# MCU.net
KiCad netlist of a schematic drawn in Altium Designer
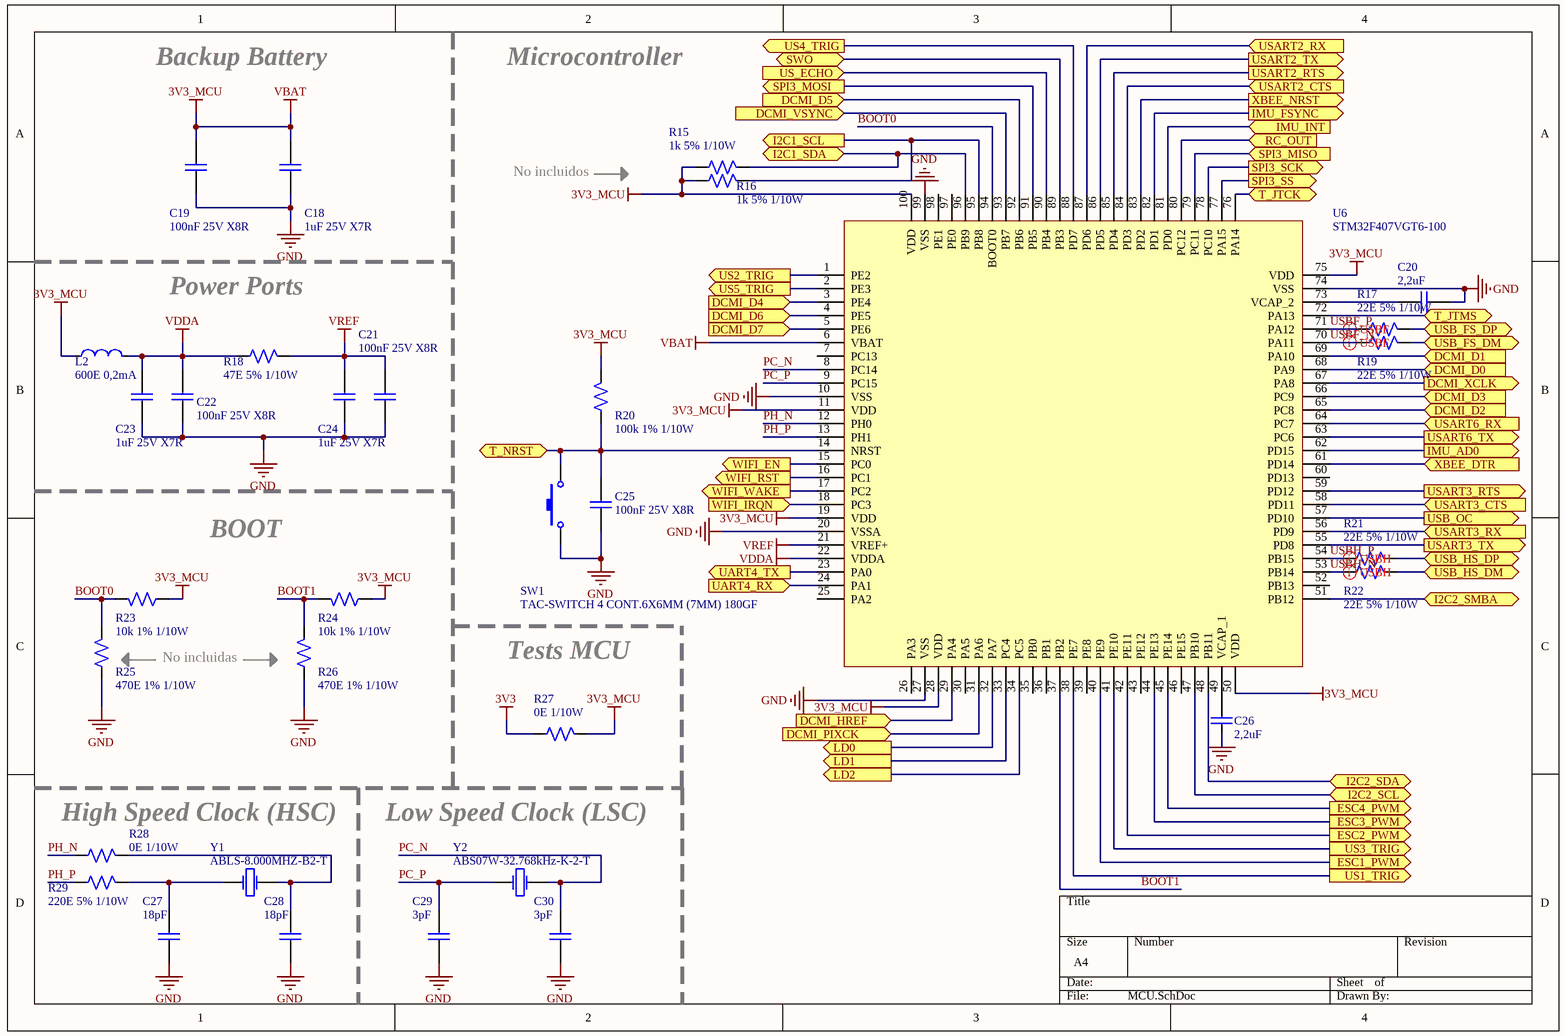
[diagram p0: MCU.SchDoc]

(export (version "E")
  (design (tool "Eeschema 10.0.6"))
  (components
    (comp (ref "C18")
      (value "1uF 25V X7R")
      (footprint "C0603")
      (description "Capacitor de placas paralelas")
      (libsource (lib "HW_Dron_V2") (part "Capacitor"))
    )
    (comp (ref "C19")
      (value "100nF 25V X8R")
      (footprint "C0603")
      (description "Capacitor de placas paralelas")
      (libsource (lib "HW_Dron_V2") (part "Capacitor"))
    )
    (comp (ref "C20")
      (value "2,2uF 16V X7R")
      (footprint "C0603")
      (description "Capacitor de placas paralelas")
      (fields (field (name "VALOR") "2,2uF"))
      (libsource (lib "HW_Dron_V2") (part "Capacitor"))
    )
    (comp (ref "C21")
      (value "100nF 25V X8R")
      (footprint "C0603")
      (description "Capacitor de placas paralelas")
      (libsource (lib "HW_Dron_V2") (part "Capacitor"))
    )
    (comp (ref "C22")
      (value "100nF 25V X8R")
      (footprint "C0603")
      (description "Capacitor de placas paralelas")
      (libsource (lib "HW_Dron_V2") (part "Capacitor"))
    )
    (comp (ref "C23")
      (value "1uF 25V X7R")
      (footprint "C0603")
      (description "Capacitor de placas paralelas")
      (libsource (lib "HW_Dron_V2") (part "Capacitor"))
    )
    (comp (ref "C24")
      (value "1uF 25V X7R")
      (footprint "C0603")
      (description "Capacitor de placas paralelas")
      (libsource (lib "HW_Dron_V2") (part "Capacitor"))
    )
    (comp (ref "C25")
      (value "100nF 25V X8R")
      (footprint "C0603")
      (description "Capacitor de placas paralelas")
      (libsource (lib "HW_Dron_V2") (part "Capacitor"))
    )
    (comp (ref "C26")
      (value "2,2uF 16V X7R")
      (footprint "C0603")
      (description "Capacitor de placas paralelas")
      (fields (field (name "VALOR") "2,2uF"))
      (libsource (lib "HW_Dron_V2") (part "Capacitor"))
    )
    (comp (ref "C27")
      (value "18pF 50V COG 5%")
      (footprint "C0603")
      (description "Capacitor de placas paralelas")
      (fields (field (name "VALOR") "18pF"))
      (libsource (lib "HW_Dron_V2") (part "Capacitor"))
    )
    (comp (ref "C28")
      (value "18pF 50V COG 5%")
      (footprint "C0603")
      (description "Capacitor de placas paralelas")
      (fields (field (name "VALOR") "18pF"))
      (libsource (lib "HW_Dron_V2") (part "Capacitor"))
    )
    (comp (ref "C29")
      (value "3pF 50V COG 5%")
      (footprint "C0603")
      (description "Capacitor de placas paralelas")
      (fields (field (name "VALOR") "3pF"))
      (libsource (lib "HW_Dron_V2") (part "Capacitor"))
    )
    (comp (ref "C30")
      (value "3pF 50V COG 5%")
      (footprint "C0603")
      (description "Capacitor de placas paralelas")
      (fields (field (name "VALOR") "3pF"))
      (libsource (lib "HW_Dron_V2") (part "Capacitor"))
    )
    (comp (ref "L2")
      (value "600E 0,2mA")
      (footprint "L0805")
      (description "Inductor")
      (fields (field (name "VALOR") "600E 0,2mA"))
      (libsource (lib "HW_Dron_V2") (part "Inductor"))
    )
    (comp (ref "R15")
      (value "1k 5% 1/10W")
      (footprint "R0603")
      (description "Resistencia")
      (libsource (lib "HW_Dron_V2") (part "Resistor"))
    )
    (comp (ref "R16")
      (value "1k 5% 1/10W")
      (footprint "R0603")
      (description "Resistencia")
      (libsource (lib "HW_Dron_V2") (part "Resistor"))
    )
    (comp (ref "R17")
      (value "22E 5% 1/10W")
      (footprint "R0603")
      (description "Resistencia")
      (libsource (lib "HW_Dron_V2") (part "Resistor"))
    )
    (comp (ref "R18")
      (value "47E 5% 1/10W")
      (footprint "R0603")
      (description "Resistencia")
      (libsource (lib "HW_Dron_V2") (part "Resistor"))
    )
    (comp (ref "R19")
      (value "22E 5% 1/10W")
      (footprint "R0603")
      (description "Resistencia")
      (libsource (lib "HW_Dron_V2") (part "Resistor"))
    )
    (comp (ref "R20")
      (value "100k 1% 1/10W")
      (footprint "R0603")
      (description "Resistencia")
      (libsource (lib "HW_Dron_V2") (part "Resistor"))
    )
    (comp (ref "R21")
      (value "22E 5% 1/10W")
      (footprint "R0603")
      (description "Resistencia")
      (libsource (lib "HW_Dron_V2") (part "Resistor"))
    )
    (comp (ref "R22")
      (value "22E 5% 1/10W")
      (footprint "R0603")
      (description "Resistencia")
      (libsource (lib "HW_Dron_V2") (part "Resistor"))
    )
    (comp (ref "R23")
      (value "10k 1% 1/10W")
      (footprint "R0603")
      (description "Resistencia")
      (libsource (lib "HW_Dron_V2") (part "Resistor"))
    )
    (comp (ref "R24")
      (value "10k 1% 1/10W")
      (footprint "R0603")
      (description "Resistencia")
      (libsource (lib "HW_Dron_V2") (part "Resistor"))
    )
    (comp (ref "R25")
      (value "470E 1% 1/10W")
      (footprint "R0603")
      (description "Resistencia")
      (libsource (lib "HW_Dron_V2") (part "Resistor"))
    )
    (comp (ref "R26")
      (value "470E 1% 1/10W")
      (footprint "R0603")
      (description "Resistencia")
      (libsource (lib "HW_Dron_V2") (part "Resistor"))
    )
    (comp (ref "R27")
      (value "0E 1/10W")
      (footprint "R0805")
      (description "Resistencia")
      (libsource (lib "HW_Dron_V2") (part "Resistor"))
    )
    (comp (ref "R28")
      (value "0E 1/10W")
      (footprint "R0603")
      (description "Resistencia")
      (libsource (lib "HW_Dron_V2") (part "Resistor"))
    )
    (comp (ref "R29")
      (value "220E 5% 1/10W")
      (footprint "R0603")
      (description "Resistencia")
      (libsource (lib "HW_Dron_V2") (part "Resistor"))
    )
    (comp (ref "SW1")
      (value "TAC-SWITCH 4 CONT.6X6MM (7MM) 180GF")
      (footprint "TAC_SW_4")
      (description "Pulsador de 4 pines")
      (libsource (lib "HW_Dron_V2") (part "TAC_SWITCH_4"))
    )
    (comp (ref "U6")
      (value "STM32F407VGT6-100")
      (footprint "QFP100")
      (description "Microcontrolador STM32F407VGT6 100 pines")
      (libsource (lib "HW_Dron_V2") (part "STM32F407VGT6_100"))
    )
    (comp (ref "Y1")
      (value "ABLS-8.000MHZ-B2-T")
      (footprint "ABLS")
      (description "Resonador cerámico")
      (libsource (lib "HW_Dron_V2") (part "XTAL"))
    )
    (comp (ref "Y2")
      (value "ABS07W-32.768kHz-K-2-T")
      (footprint "ABS07W")
      (description "Resonador cerámico")
      (libsource (lib "HW_Dron_V2") (part "XTAL"))
    )
  )
  (nets
    (net (code "1") (name "/BOOT0") (class "Default")
      (node (ref "R23") (pin "2") (pinfunction "2_2") (pintype "passive"))
      (node (ref "R25") (pin "2") (pinfunction "2_2") (pintype "passive"))
      (node (ref "U6") (pin "94") (pinfunction "BOOT0_94") (pintype "passive"))
    )
    (net (code "2") (name "/BOOT1") (class "Default")
      (node (ref "R24") (pin "2") (pinfunction "2_2") (pintype "passive"))
      (node (ref "R26") (pin "2") (pinfunction "2_2") (pintype "passive"))
      (node (ref "U6") (pin "37") (pinfunction "PB2_37") (pintype "passive"))
    )
    (net (code "3") (name "/DCMI_D0") (class "Default")
      (node (ref "U6") (pin "68") (pinfunction "PA9_68") (pintype "passive"))
    )
    (net (code "4") (name "/DCMI_D1") (class "Default")
      (node (ref "U6") (pin "69") (pinfunction "PA10_69") (pintype "passive"))
    )
    (net (code "5") (name "/DCMI_D2") (class "Default")
      (node (ref "U6") (pin "65") (pinfunction "PC8_65") (pintype "passive"))
    )
    (net (code "6") (name "/DCMI_D3") (class "Default")
      (node (ref "U6") (pin "66") (pinfunction "PC9_66") (pintype "passive"))
    )
    (net (code "7") (name "/DCMI_D4") (class "Default")
      (node (ref "U6") (pin "3") (pinfunction "PE4_3") (pintype "passive"))
    )
    (net (code "8") (name "/DCMI_D5") (class "Default")
      (node (ref "U6") (pin "92") (pinfunction "PB6_92") (pintype "passive"))
    )
    (net (code "9") (name "/DCMI_D6") (class "Default")
      (node (ref "U6") (pin "4") (pinfunction "PE5_4") (pintype "passive"))
    )
    (net (code "10") (name "/DCMI_D7") (class "Default")
      (node (ref "U6") (pin "5") (pinfunction "PE6_5") (pintype "passive"))
    )
    (net (code "11") (name "/DCMI_HREF") (class "Default")
      (node (ref "U6") (pin "29") (pinfunction "PA4_29") (pintype "passive"))
    )
    (net (code "12") (name "/DCMI_PIXCK") (class "Default")
      (node (ref "U6") (pin "31") (pinfunction "PA6_31") (pintype "passive"))
    )
    (net (code "13") (name "/DCMI_VSYNC") (class "Default")
      (node (ref "U6") (pin "93") (pinfunction "PB7_93") (pintype "passive"))
    )
    (net (code "14") (name "/DCMI_XCLK") (class "Default")
      (node (ref "U6") (pin "67") (pinfunction "PA8_67") (pintype "passive"))
    )
    (net (code "15") (name "/ESC1_PWM") (class "Default")
      (node (ref "U6") (pin "40") (pinfunction "PE9_40") (pintype "passive"))
    )
    (net (code "16") (name "/ESC2_PWM") (class "Default")
      (node (ref "U6") (pin "42") (pinfunction "PE11_42") (pintype "passive"))
    )
    (net (code "17") (name "/ESC3_PWM") (class "Default")
      (node (ref "U6") (pin "44") (pinfunction "PE13_44") (pintype "passive"))
    )
    (net (code "18") (name "/ESC4_PWM") (class "Default")
      (node (ref "U6") (pin "45") (pinfunction "PE14_45") (pintype "passive"))
    )
    (net (code "19") (name "/I2C1_SCL") (class "Default")
      (node (ref "R16") (pin "2") (pinfunction "2_2") (pintype "passive"))
      (node (ref "U6") (pin "95") (pinfunction "PB8_95") (pintype "passive"))
    )
    (net (code "20") (name "/I2C1_SDA") (class "Default")
      (node (ref "R15") (pin "2") (pinfunction "2_2") (pintype "passive"))
      (node (ref "U6") (pin "96") (pinfunction "PB9_96") (pintype "passive"))
    )
    (net (code "21") (name "/I2C2_SCL") (class "Default")
      (node (ref "U6") (pin "47") (pinfunction "PB10_47") (pintype "passive"))
    )
    (net (code "22") (name "/I2C2_SDA") (class "Default")
      (node (ref "U6") (pin "48") (pinfunction "PB11_48") (pintype "passive"))
    )
    (net (code "23") (name "/I2C2_SMBA") (class "Default")
      (node (ref "U6") (pin "51") (pinfunction "PB12_51") (pintype "passive"))
    )
    (net (code "24") (name "/IMU_AD0") (class "Default")
      (node (ref "U6") (pin "62") (pinfunction "PD15_62") (pintype "passive"))
    )
    (net (code "25") (name "/IMU_FSYNC") (class "Default")
      (node (ref "U6") (pin "82") (pinfunction "PD1_82") (pintype "passive"))
    )
    (net (code "26") (name "/IMU_INT") (class "Default")
      (node (ref "U6") (pin "81") (pinfunction "PD0_81") (pintype "passive"))
    )
    (net (code "27") (name "/LD0") (class "Default")
      (node (ref "U6") (pin "32") (pinfunction "PA7_32") (pintype "passive"))
    )
    (net (code "28") (name "/LD1") (class "Default")
      (node (ref "U6") (pin "33") (pinfunction "PC4_33") (pintype "passive"))
    )
    (net (code "29") (name "/LD2") (class "Default")
      (node (ref "U6") (pin "34") (pinfunction "PC5_34") (pintype "passive"))
    )
    (net (code "30") (name "/PC_N") (class "Default")
      (node (ref "C30") (pin "1") (pinfunction "1_1") (pintype "passive"))
      (node (ref "U6") (pin "8") (pinfunction "PC14_8") (pintype "passive"))
      (node (ref "Y2") (pin "2") (pinfunction "2_2") (pintype "passive"))
    )
    (net (code "31") (name "/PC_P") (class "Default")
      (node (ref "C29") (pin "1") (pinfunction "1_1") (pintype "passive"))
      (node (ref "U6") (pin "9") (pinfunction "PC15_9") (pintype "passive"))
      (node (ref "Y2") (pin "1") (pinfunction "1_1") (pintype "passive"))
    )
    (net (code "32") (name "/PH_N") (class "Default")
      (node (ref "R28") (pin "1") (pinfunction "1_1") (pintype "passive"))
      (node (ref "U6") (pin "12") (pinfunction "PH0_12") (pintype "passive"))
    )
    (net (code "33") (name "/PH_P") (class "Default")
      (node (ref "R29") (pin "1") (pinfunction "1_1") (pintype "passive"))
      (node (ref "U6") (pin "13") (pinfunction "PH1_13") (pintype "passive"))
    )
    (net (code "34") (name "/RC_OUT") (class "Default")
      (node (ref "U6") (pin "80") (pinfunction "PC12_80") (pintype "passive"))
    )
    (net (code "35") (name "/SPI3_MISO") (class "Default")
      (node (ref "U6") (pin "79") (pinfunction "PC11_79") (pintype "passive"))
    )
    (net (code "36") (name "/SPI3_MOSI") (class "Default")
      (node (ref "U6") (pin "91") (pinfunction "PB5_91") (pintype "passive"))
    )
    (net (code "37") (name "/SPI3_SCK") (class "Default")
      (node (ref "U6") (pin "78") (pinfunction "PC10_78") (pintype "passive"))
    )
    (net (code "38") (name "/SPI3_SS") (class "Default")
      (node (ref "U6") (pin "77") (pinfunction "PA15_77") (pintype "passive"))
    )
    (net (code "39") (name "/SWO") (class "Default")
      (node (ref "U6") (pin "89") (pinfunction "PB3_89") (pintype "passive"))
    )
    (net (code "40") (name "/T_JTCK") (class "Default")
      (node (ref "U6") (pin "76") (pinfunction "PA14_76") (pintype "passive"))
    )
    (net (code "41") (name "/T_JTMS") (class "Default")
      (node (ref "U6") (pin "72") (pinfunction "PA13_72") (pintype "passive"))
    )
    (net (code "42") (name "/T_NRST") (class "Default")
      (node (ref "C25") (pin "1") (pinfunction "1_1") (pintype "passive"))
      (node (ref "R20") (pin "1") (pinfunction "1_1") (pintype "passive"))
      (node (ref "SW1") (pin "2") (pinfunction "2_2") (pintype "passive"))
      (node (ref "U6") (pin "14") (pinfunction "NRST_14") (pintype "passive"))
    )
    (net (code "43") (name "/UART4_RX") (class "Default")
      (node (ref "U6") (pin "24") (pinfunction "PA1_24") (pintype "passive"))
    )
    (net (code "44") (name "/UART4_TX") (class "Default")
      (node (ref "U6") (pin "23") (pinfunction "PA0_23") (pintype "passive"))
    )
    (net (code "45") (name "/US1_TRIG") (class "Default")
      (node (ref "U6") (pin "38") (pinfunction "PE7_38") (pintype "passive"))
    )
    (net (code "46") (name "/US2_TRIG") (class "Default")
      (node (ref "U6") (pin "1") (pinfunction "PE2_1") (pintype "passive"))
    )
    (net (code "47") (name "/US3_TRIG") (class "Default")
      (node (ref "U6") (pin "41") (pinfunction "PE10_41") (pintype "passive"))
    )
    (net (code "48") (name "/US4_TRIG") (class "Default")
      (node (ref "U6") (pin "88") (pinfunction "PD7_88") (pintype "passive"))
    )
    (net (code "49") (name "/US5_TRIG") (class "Default")
      (node (ref "U6") (pin "2") (pinfunction "PE3_2") (pintype "passive"))
    )
    (net (code "50") (name "/USART2_CTS") (class "Default")
      (node (ref "U6") (pin "84") (pinfunction "PD3_84") (pintype "passive"))
    )
    (net (code "51") (name "/USART2_RTS") (class "Default")
      (node (ref "U6") (pin "85") (pinfunction "PD4_85") (pintype "passive"))
    )
    (net (code "52") (name "/USART2_RX") (class "Default")
      (node (ref "U6") (pin "87") (pinfunction "PD6_87") (pintype "passive"))
    )
    (net (code "53") (name "/USART2_TX") (class "Default")
      (node (ref "U6") (pin "86") (pinfunction "PD5_86") (pintype "passive"))
    )
    (net (code "54") (name "/USART3_CTS") (class "Default")
      (node (ref "U6") (pin "58") (pinfunction "PD11_58") (pintype "passive"))
    )
    (net (code "55") (name "/USART3_RTS") (class "Default")
      (node (ref "U6") (pin "59") (pinfunction "PD12_59") (pintype "passive"))
    )
    (net (code "56") (name "/USART3_RX") (class "Default")
      (node (ref "U6") (pin "56") (pinfunction "PD9_56") (pintype "passive"))
    )
    (net (code "57") (name "/USART3_TX") (class "Default")
      (node (ref "U6") (pin "55") (pinfunction "PD8_55") (pintype "passive"))
    )
    (net (code "58") (name "/USART6_RX") (class "Default")
      (node (ref "U6") (pin "64") (pinfunction "PC7_64") (pintype "passive"))
    )
    (net (code "59") (name "/USART6_TX") (class "Default")
      (node (ref "U6") (pin "63") (pinfunction "PC6_63") (pintype "passive"))
    )
    (net (code "60") (name "/USBF_N") (class "Default")
      (node (ref "R19") (pin "1") (pinfunction "1_1") (pintype "passive"))
      (node (ref "U6") (pin "70") (pinfunction "PA11_70") (pintype "passive"))
    )
    (net (code "61") (name "/USBF_P") (class "Default")
      (node (ref "R17") (pin "1") (pinfunction "1_1") (pintype "passive"))
      (node (ref "U6") (pin "71") (pinfunction "PA12_71") (pintype "passive"))
    )
    (net (code "62") (name "/USBH_N") (class "Default")
      (node (ref "R22") (pin "1") (pinfunction "1_1") (pintype "passive"))
      (node (ref "U6") (pin "53") (pinfunction "PB14_53") (pintype "passive"))
    )
    (net (code "63") (name "/USBH_P") (class "Default")
      (node (ref "R21") (pin "1") (pinfunction "1_1") (pintype "passive"))
      (node (ref "U6") (pin "54") (pinfunction "PB15_54") (pintype "passive"))
    )
    (net (code "64") (name "/USB_FS_DM") (class "Default")
      (node (ref "R19") (pin "2") (pinfunction "2_2") (pintype "passive"))
    )
    (net (code "65") (name "/USB_FS_DP") (class "Default")
      (node (ref "R17") (pin "2") (pinfunction "2_2") (pintype "passive"))
    )
    (net (code "66") (name "/USB_HS_DM") (class "Default")
      (node (ref "R22") (pin "2") (pinfunction "2_2") (pintype "passive"))
    )
    (net (code "67") (name "/USB_HS_DP") (class "Default")
      (node (ref "R21") (pin "2") (pinfunction "2_2") (pintype "passive"))
    )
    (net (code "68") (name "/USB_OC") (class "Default")
      (node (ref "U6") (pin "57") (pinfunction "PD10_57") (pintype "passive"))
    )
    (net (code "69") (name "/US_ECHO") (class "Default")
      (node (ref "U6") (pin "90") (pinfunction "PB4_90") (pintype "passive"))
    )
    (net (code "70") (name "/WIFI_EN") (class "Default")
      (node (ref "U6") (pin "15") (pinfunction "PC0_15") (pintype "passive"))
    )
    (net (code "71") (name "/WIFI_IRQN") (class "Default")
      (node (ref "U6") (pin "18") (pinfunction "PC3_18") (pintype "passive"))
    )
    (net (code "72") (name "/WIFI_RST") (class "Default")
      (node (ref "U6") (pin "16") (pinfunction "PC1_16") (pintype "passive"))
    )
    (net (code "73") (name "/WIFI_WAKE") (class "Default")
      (node (ref "U6") (pin "17") (pinfunction "PC2_17") (pintype "passive"))
    )
    (net (code "74") (name "/XBEE_DTR") (class "Default")
      (node (ref "U6") (pin "61") (pinfunction "PD14_61") (pintype "passive"))
    )
    (net (code "75") (name "/XBEE_NRST") (class "Default")
      (node (ref "U6") (pin "83") (pinfunction "PD2_83") (pintype "passive"))
    )
    (net (code "76") (name "3V3") (class "Default")
      (node (ref "R27") (pin "1") (pinfunction "1_1") (pintype "passive"))
    )
    (net (code "77") (name "3V3_MCU") (class "Default")
      (node (ref "C18") (pin "1") (pinfunction "1_1") (pintype "passive"))
      (node (ref "C19") (pin "1") (pinfunction "1_1") (pintype "passive"))
      (node (ref "L2") (pin "1") (pinfunction "1_1") (pintype "passive"))
      (node (ref "R15") (pin "1") (pinfunction "1_1") (pintype "passive"))
      (node (ref "R16") (pin "1") (pinfunction "1_1") (pintype "passive"))
      (node (ref "R20") (pin "2") (pinfunction "2_2") (pintype "passive"))
      (node (ref "R23") (pin "1") (pinfunction "1_1") (pintype "passive"))
      (node (ref "R24") (pin "1") (pinfunction "1_1") (pintype "passive"))
      (node (ref "R27") (pin "2") (pinfunction "2_2") (pintype "passive"))
      (node (ref "U6") (pin "100") (pinfunction "VDD_100") (pintype "passive"))
      (node (ref "U6") (pin "11") (pinfunction "VDD_11") (pintype "passive"))
      (node (ref "U6") (pin "19") (pinfunction "VDD_19") (pintype "passive"))
      (node (ref "U6") (pin "28") (pinfunction "VDD_28") (pintype "passive"))
      (node (ref "U6") (pin "50") (pinfunction "VDD_50") (pintype "passive"))
      (node (ref "U6") (pin "6") (pinfunction "VBAT_6") (pintype "passive"))
      (node (ref "U6") (pin "75") (pinfunction "VDD_75") (pintype "passive"))
    )
    (net (code "78") (name "GND") (class "Default")
      (node (ref "C18") (pin "2") (pinfunction "2_2") (pintype "passive"))
      (node (ref "C19") (pin "2") (pinfunction "2_2") (pintype "passive"))
      (node (ref "C20") (pin "2") (pinfunction "2_2") (pintype "passive"))
      (node (ref "C21") (pin "2") (pinfunction "2_2") (pintype "passive"))
      (node (ref "C22") (pin "2") (pinfunction "2_2") (pintype "passive"))
      (node (ref "C23") (pin "2") (pinfunction "2_2") (pintype "passive"))
      (node (ref "C24") (pin "2") (pinfunction "2_2") (pintype "passive"))
      (node (ref "C25") (pin "2") (pinfunction "2_2") (pintype "passive"))
      (node (ref "C26") (pin "2") (pinfunction "2_2") (pintype "passive"))
      (node (ref "C27") (pin "2") (pinfunction "2_2") (pintype "passive"))
      (node (ref "C28") (pin "2") (pinfunction "2_2") (pintype "passive"))
      (node (ref "C29") (pin "2") (pinfunction "2_2") (pintype "passive"))
      (node (ref "C30") (pin "2") (pinfunction "2_2") (pintype "passive"))
      (node (ref "R25") (pin "1") (pinfunction "1_1") (pintype "passive"))
      (node (ref "R26") (pin "1") (pinfunction "1_1") (pintype "passive"))
      (node (ref "SW1") (pin "1") (pinfunction "1_1") (pintype "passive"))
      (node (ref "U6") (pin "10") (pinfunction "VSS_10") (pintype "passive"))
      (node (ref "U6") (pin "20") (pinfunction "VSSA_20") (pintype "passive"))
      (node (ref "U6") (pin "27") (pinfunction "VSS_27") (pintype "passive"))
      (node (ref "U6") (pin "74") (pinfunction "VSS_74") (pintype "passive"))
      (node (ref "U6") (pin "99") (pinfunction "VSS_99") (pintype "passive"))
    )
    (net (code "79") (name "Net-(C27-Pad1)") (class "Default")
      (node (ref "C27") (pin "1") (pinfunction "1_1") (pintype "passive"))
      (node (ref "R29") (pin "2") (pinfunction "2_2") (pintype "passive"))
      (node (ref "Y1") (pin "1") (pinfunction "1_1") (pintype "passive"))
    )
    (net (code "80") (name "Net-(C28-Pad1)") (class "Default")
      (node (ref "C28") (pin "1") (pinfunction "1_1") (pintype "passive"))
      (node (ref "R28") (pin "2") (pinfunction "2_2") (pintype "passive"))
      (node (ref "Y1") (pin "2") (pinfunction "2_2") (pintype "passive"))
    )
    (net (code "81") (name "Net-(U6-VCAP_1)") (class "Default")
      (node (ref "C26") (pin "1") (pinfunction "1_1") (pintype "passive"))
      (node (ref "U6") (pin "49") (pinfunction "VCAP_1_49") (pintype "passive"))
    )
    (net (code "82") (name "Net-(U6-VCAP_2)") (class "Default")
      (node (ref "C20") (pin "1") (pinfunction "1_1") (pintype "passive"))
      (node (ref "U6") (pin "73") (pinfunction "VCAP_2_73") (pintype "passive"))
    )
    (net (code "83") (name "VDDA") (class "Default")
      (node (ref "C22") (pin "1") (pinfunction "1_1") (pintype "passive"))
      (node (ref "C23") (pin "1") (pinfunction "1_1") (pintype "passive"))
      (node (ref "L2") (pin "2") (pinfunction "2_2") (pintype "passive"))
      (node (ref "R18") (pin "1") (pinfunction "1_1") (pintype "passive"))
      (node (ref "U6") (pin "22") (pinfunction "VDDA_22") (pintype "passive"))
    )
    (net (code "84") (name "VREF") (class "Default")
      (node (ref "C21") (pin "1") (pinfunction "1_1") (pintype "passive"))
      (node (ref "C24") (pin "1") (pinfunction "1_1") (pintype "passive"))
      (node (ref "R18") (pin "2") (pinfunction "2_2") (pintype "passive"))
      (node (ref "U6") (pin "21") (pinfunction "VREF+_21") (pintype "passive"))
    )
    (net (code "85") (name "unconnected-(U6-PA2-Pad25)") (class "Default")
      (node (ref "U6") (pin "25") (pinfunction "PA2_25") (pintype "passive"))
    )
    (net (code "86") (name "unconnected-(U6-PA3-Pad26)") (class "Default")
      (node (ref "U6") (pin "26") (pinfunction "PA3_26") (pintype "passive"))
    )
    (net (code "87") (name "unconnected-(U6-PA5-Pad30)") (class "Default")
      (node (ref "U6") (pin "30") (pinfunction "PA5_30") (pintype "passive"))
    )
    (net (code "88") (name "unconnected-(U6-PB0-Pad35)") (class "Default")
      (node (ref "U6") (pin "35") (pinfunction "PB0_35") (pintype "passive"))
    )
    (net (code "89") (name "unconnected-(U6-PB1-Pad36)") (class "Default")
      (node (ref "U6") (pin "36") (pinfunction "PB1_36") (pintype "passive"))
    )
    (net (code "90") (name "unconnected-(U6-PB13-Pad52)") (class "Default")
      (node (ref "U6") (pin "52") (pinfunction "PB13_52") (pintype "passive"))
    )
    (net (code "91") (name "unconnected-(U6-PC13-Pad7)") (class "Default")
      (node (ref "U6") (pin "7") (pinfunction "PC13_7") (pintype "passive"))
    )
    (net (code "92") (name "unconnected-(U6-PD13-Pad60)") (class "Default")
      (node (ref "U6") (pin "60") (pinfunction "PD13_60") (pintype "passive"))
    )
    (net (code "93") (name "unconnected-(U6-PE0-Pad97)") (class "Default")
      (node (ref "U6") (pin "97") (pinfunction "PE0_97") (pintype "passive"))
    )
    (net (code "94") (name "unconnected-(U6-PE1-Pad98)") (class "Default")
      (node (ref "U6") (pin "98") (pinfunction "PE1_98") (pintype "passive"))
    )
    (net (code "95") (name "unconnected-(U6-PE8-Pad39)") (class "Default")
      (node (ref "U6") (pin "39") (pinfunction "PE8_39") (pintype "passive"))
    )
    (net (code "96") (name "unconnected-(U6-PE12-Pad43)") (class "Default")
      (node (ref "U6") (pin "43") (pinfunction "PE12_43") (pintype "passive"))
    )
    (net (code "97") (name "unconnected-(U6-PE15-Pad46)") (class "Default")
      (node (ref "U6") (pin "46") (pinfunction "PE15_46") (pintype "passive"))
    )
  )
)
